# coilcube.net
KiCad netlist of a schematic drawn in EAGLE
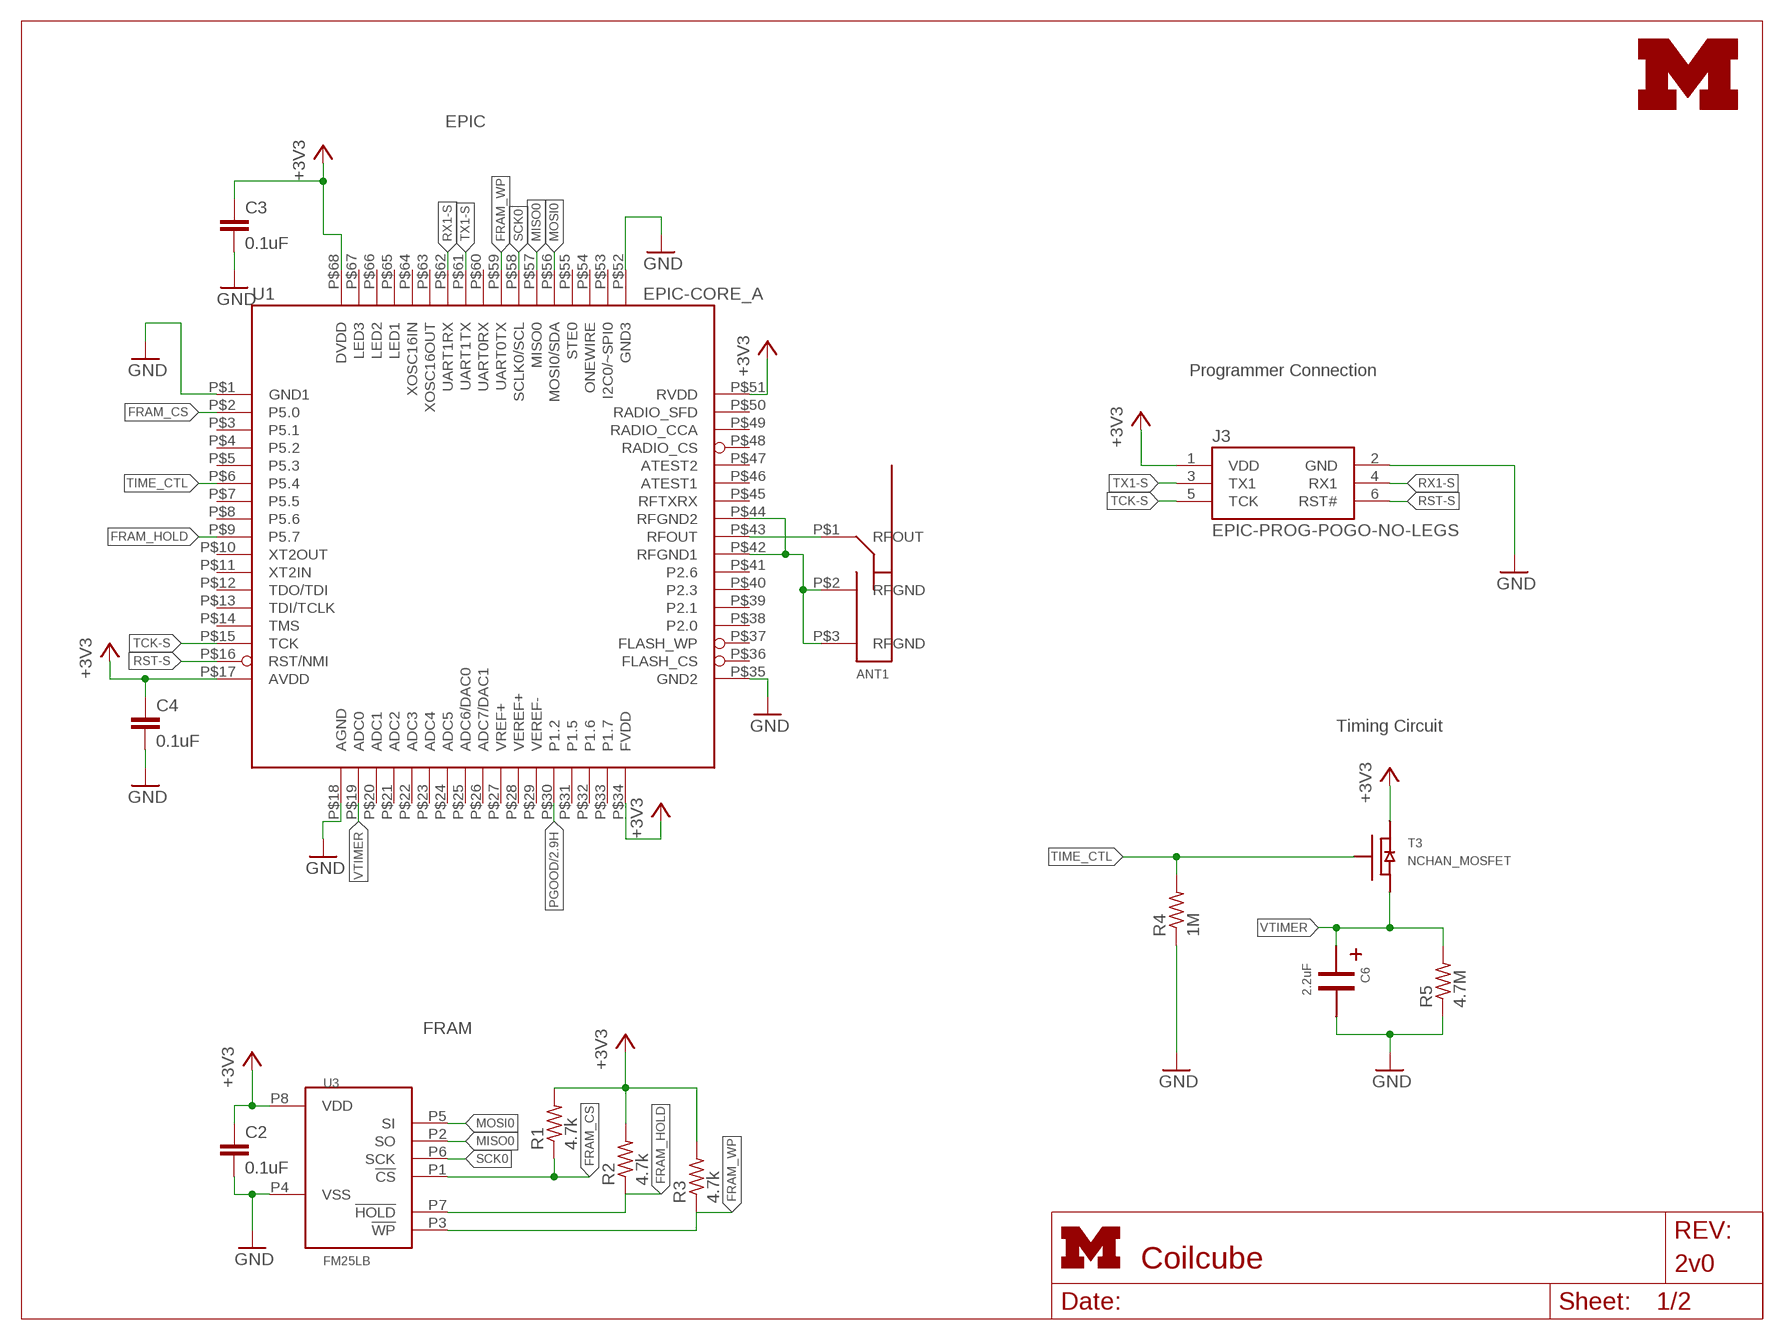
[diagram p0: schematic, sheet 1]
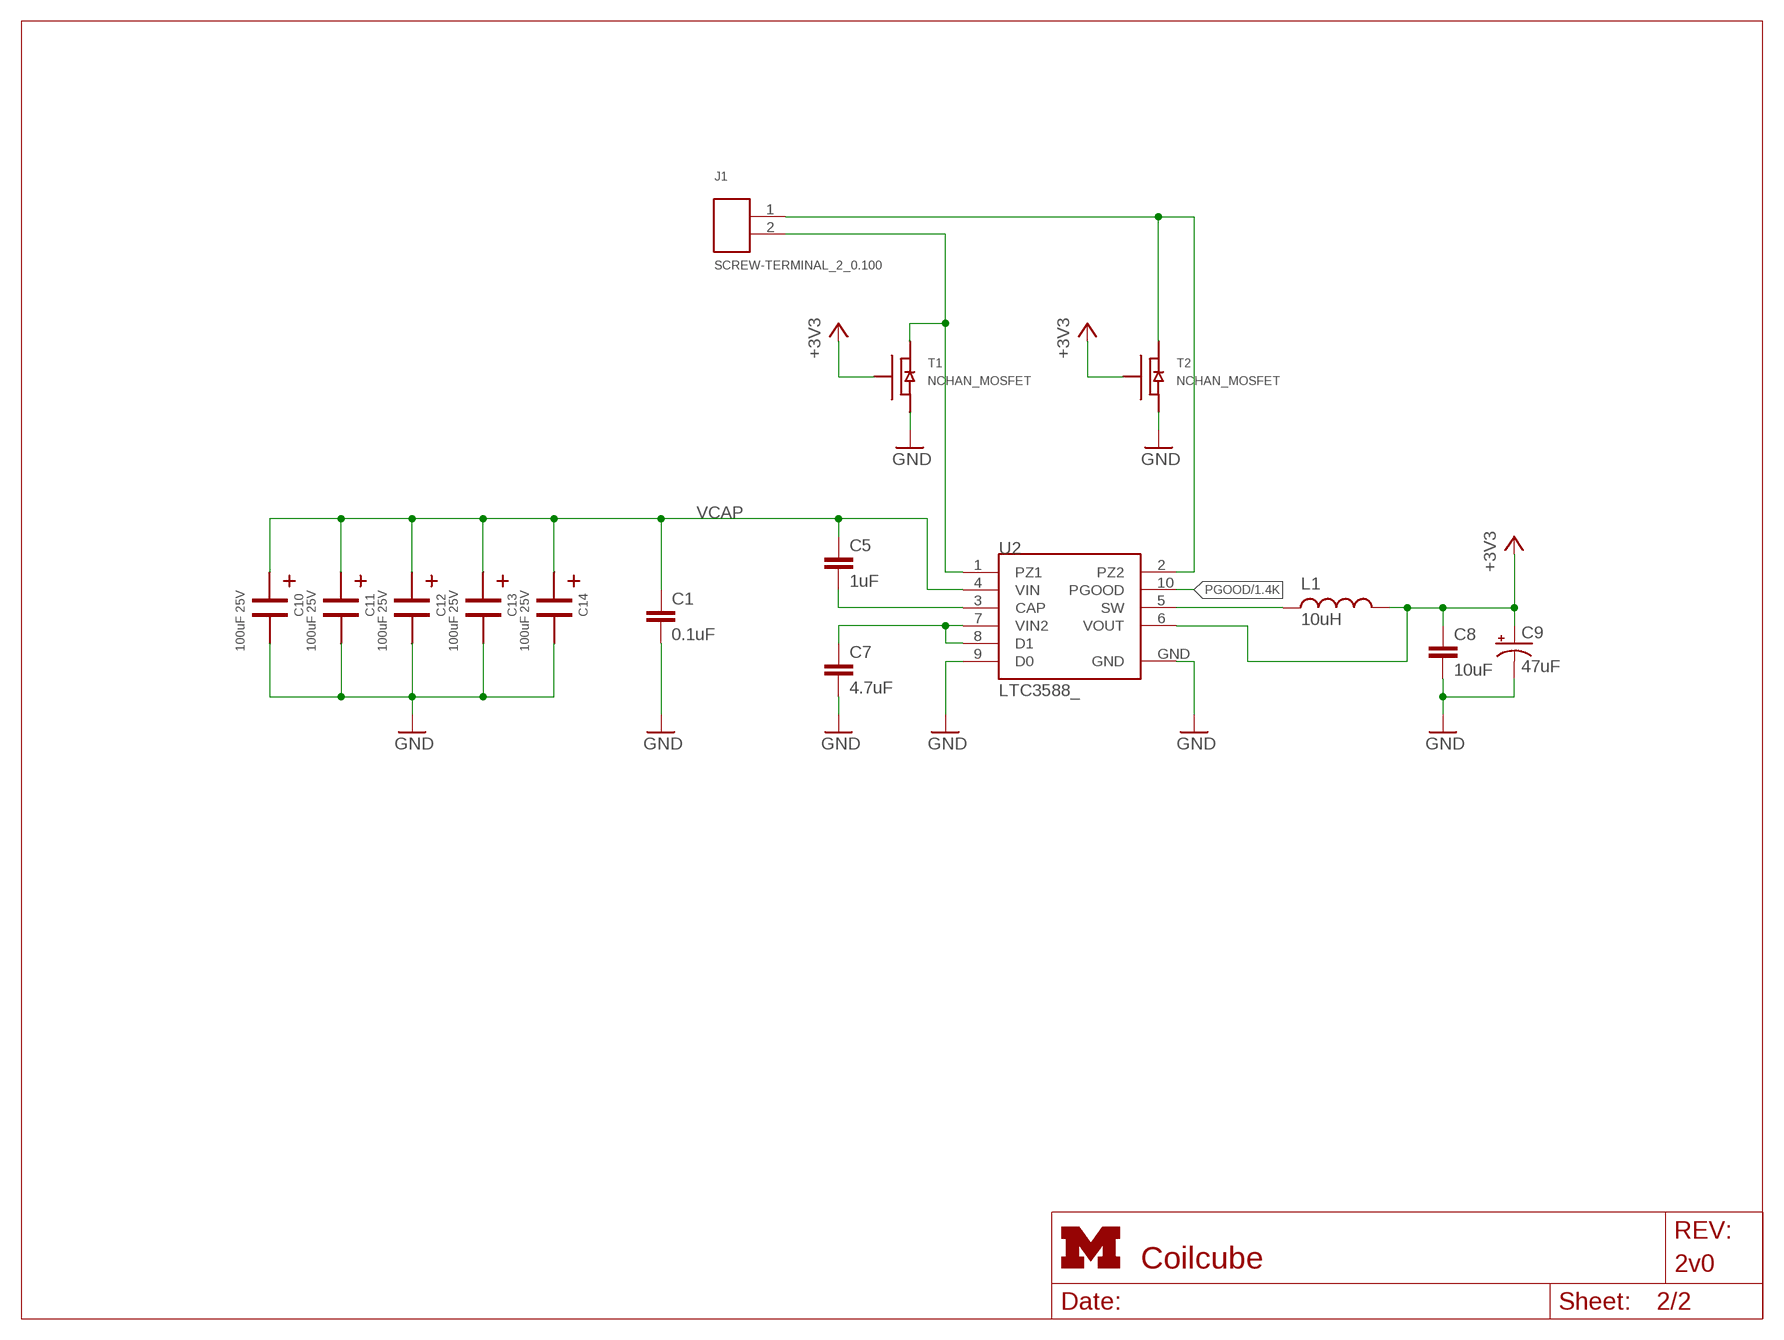
[diagram p1: schematic, sheet 2]

(export (version "E")
  (design (tool "Eeschema 10.0.6"))
  (components
    (comp (ref "ANT1")
      (value "PIFA-2.4GHZ")
      (footprint "eagle-import:PIFA-2.4GHZ")
      (libsource (lib "eagle-import") (part "PIFA-2.4GHZ"))
    )
    (comp (ref "C2")
      (value "0.1uF")
      (footprint "eagle-import:C0603")
      (libsource (lib "eagle-import") (part "C-EUC0603"))
    )
    (comp (ref "C3")
      (value "0.1uF")
      (footprint "eagle-import:C0603")
      (libsource (lib "eagle-import") (part "C-EUC0603"))
    )
    (comp (ref "C4")
      (value "0.1uF")
      (footprint "eagle-import:C0603")
      (libsource (lib "eagle-import") (part "C-EUC0603"))
    )
    (comp (ref "C6")
      (value "2.2uF")
      (footprint "eagle-import:CPOL_EEA_1MM5")
      (libsource (lib "eagle-import") (part "CAP_POLEA1MM5"))
    )
    (comp (ref "J3")
      (value "EPIC-PROG-POGO-NO-LEGS")
      (footprint "eagle-import:TC2030-IDC-NL")
      (libsource (lib "eagle-import") (part "EPIC-PROG-POGO-NO-LEGS"))
    )
    (comp (ref "R1")
      (value "4.7k")
      (footprint "eagle-import:R0603")
      (libsource (lib "eagle-import") (part "R-US_R0603"))
    )
    (comp (ref "R2")
      (value "4.7k")
      (footprint "eagle-import:R0603")
      (libsource (lib "eagle-import") (part "R-US_R0603"))
    )
    (comp (ref "R3")
      (value "4.7k")
      (footprint "eagle-import:R0603")
      (libsource (lib "eagle-import") (part "R-US_R0603"))
    )
    (comp (ref "R4")
      (value "1M")
      (footprint "eagle-import:R0603")
      (libsource (lib "eagle-import") (part "R-US_R0603"))
    )
    (comp (ref "R5")
      (value "4.7M")
      (footprint "eagle-import:R0603")
      (libsource (lib "eagle-import") (part "R-US_R0603"))
    )
    (comp (ref "T3")
      (value "NCHAN_MOSFET")
      (footprint "eagle-import:NCHAN_MOSFET")
      (libsource (lib "eagle-import") (part "NCHAN_MOSFET"))
    )
    (comp (ref "U$1")
      (value "UMICH_SOLID_MEDIUM")
      (footprint "eagle-import:UMICH_SOLID_200MIL")
      (libsource (lib "eagle-import") (part "UMICH_SOLID_MEDIUM"))
    )
    (comp (ref "U1")
      (value "EPIC-CORE_A")
      (footprint "eagle-import:EPIC-LCC68")
      (libsource (lib "eagle-import") (part "EPIC-CORE_A"))
    )
    (comp (ref "U3")
      (value "FM25LB")
      (footprint "eagle-import:SOIC_8")
      (libsource (lib "eagle-import") (part "FM25LB"))
    )
    (comp (ref "C1")
      (value "0.1uF")
      (footprint "eagle-import:C0603")
      (libsource (lib "eagle-import") (part "C-EUC0603"))
    )
    (comp (ref "C5")
      (value "1uF")
      (footprint "eagle-import:C0603")
      (libsource (lib "eagle-import") (part "C-EUC0603"))
    )
    (comp (ref "C7")
      (value "4.7uF")
      (footprint "eagle-import:C0603")
      (libsource (lib "eagle-import") (part "C-EUC0603"))
    )
    (comp (ref "C8")
      (value "10uF")
      (footprint "eagle-import:C1206")
      (libsource (lib "eagle-import") (part "C-EUC1206"))
    )
    (comp (ref "C9")
      (value "47uF")
      (footprint "eagle-import:EIA3216")
      (libsource (lib "eagle-import") (part "CAP_POL1206"))
    )
    (comp (ref "C10")
      (value "100uF 25V")
      (footprint "eagle-import:2917_CAP_POL")
      (libsource (lib "eagle-import") (part "2917_CAP_POL"))
    )
    (comp (ref "C11")
      (value "100uF 25V")
      (footprint "eagle-import:2917_CAP_POL")
      (libsource (lib "eagle-import") (part "2917_CAP_POL"))
    )
    (comp (ref "C12")
      (value "100uF 25V")
      (footprint "eagle-import:2917_CAP_POL")
      (libsource (lib "eagle-import") (part "2917_CAP_POL"))
    )
    (comp (ref "C13")
      (value "100uF 25V")
      (footprint "eagle-import:2917_CAP_POL")
      (libsource (lib "eagle-import") (part "2917_CAP_POL"))
    )
    (comp (ref "C14")
      (value "100uF 25V")
      (footprint "eagle-import:2917_CAP_POL")
      (libsource (lib "eagle-import") (part "2917_CAP_POL"))
    )
    (comp (ref "J1")
      (value "SCREW-TERMINAL_2_0.100")
      (footprint "eagle-import:CONN_BLOCK_2")
      (libsource (lib "eagle-import") (part "SCREW-TERMINAL_2_0.100"))
    )
    (comp (ref "L1")
      (value "10uH")
      (footprint "eagle-import:1210")
      (libsource (lib "eagle-import") (part "INDUCTOR1210"))
    )
    (comp (ref "T1")
      (value "NCHAN_MOSFET")
      (footprint "eagle-import:NCHAN_MOSFET")
      (libsource (lib "eagle-import") (part "NCHAN_MOSFET"))
    )
    (comp (ref "T2")
      (value "NCHAN_MOSFET")
      (footprint "eagle-import:NCHAN_MOSFET")
      (libsource (lib "eagle-import") (part "NCHAN_MOSFET"))
    )
    (comp (ref "U2")
      (value "LTC3588_")
      (footprint "eagle-import:MSOP-10-GNDPAD")
      (libsource (lib "eagle-import") (part "LTC3588_"))
    )
  )
  (nets
    (net (code "1") (name "+3V3") (class "Default")
      (node (ref "C2") (pin "1") (pinfunction "1_1") (pintype "passive"))
      (node (ref "C3") (pin "1") (pinfunction "1_1") (pintype "passive"))
      (node (ref "C4") (pin "1") (pinfunction "1_1") (pintype "passive"))
      (node (ref "C8") (pin "1") (pinfunction "1_1") (pintype "passive"))
      (node (ref "C9") (pin "A") (pinfunction "+_A") (pintype "passive"))
      (node (ref "J3") (pin "1") (pinfunction "VDD_1") (pintype "bidirectional"))
      (node (ref "L1") (pin "2") (pinfunction "2_2") (pintype "passive"))
      (node (ref "R1") (pin "2") (pinfunction "2_2") (pintype "passive"))
      (node (ref "R2") (pin "2") (pinfunction "2_2") (pintype "passive"))
      (node (ref "R3") (pin "2") (pinfunction "2_2") (pintype "passive"))
      (node (ref "T1") (pin "G") (pinfunction "G_G") (pintype "bidirectional"))
      (node (ref "T2") (pin "G") (pinfunction "G_G") (pintype "bidirectional"))
      (node (ref "T3") (pin "D") (pinfunction "D_D") (pintype "bidirectional"))
      (node (ref "U1") (pin "P$17") (pinfunction "AVDD_P$17") (pintype "bidirectional"))
      (node (ref "U1") (pin "P$34") (pinfunction "FVDD_P$34") (pintype "bidirectional"))
      (node (ref "U1") (pin "P$51") (pinfunction "RVDD_P$51") (pintype "bidirectional"))
      (node (ref "U1") (pin "P$68") (pinfunction "DVDD_P$68") (pintype "bidirectional"))
      (node (ref "U2") (pin "6") (pinfunction "VOUT_6") (pintype "bidirectional"))
      (node (ref "U3") (pin "P8") (pinfunction "VDD_P8") (pintype "bidirectional"))
    )
    (net (code "2") (name "FRAM_CS") (class "Default")
      (node (ref "R1") (pin "1") (pinfunction "1_1") (pintype "passive"))
      (node (ref "U1") (pin "P$2") (pinfunction "P5.0_P$2") (pintype "bidirectional"))
      (node (ref "U3") (pin "P1") (pinfunction "~{CS}_P1") (pintype "bidirectional"))
    )
    (net (code "3") (name "FRAM_HOLD") (class "Default")
      (node (ref "R2") (pin "1") (pinfunction "1_1") (pintype "passive"))
      (node (ref "U1") (pin "P$9") (pinfunction "P5.7_P$9") (pintype "bidirectional"))
      (node (ref "U3") (pin "P7") (pinfunction "~{HOLD}_P7") (pintype "bidirectional"))
    )
    (net (code "4") (name "FRAM_WP") (class "Default")
      (node (ref "R3") (pin "1") (pinfunction "1_1") (pintype "passive"))
      (node (ref "U1") (pin "P$59") (pinfunction "UART0TX_P$59") (pintype "bidirectional"))
      (node (ref "U3") (pin "P3") (pinfunction "~{WP}_P3") (pintype "bidirectional"))
    )
    (net (code "5") (name "GND") (class "Default")
      (node (ref "C1") (pin "2") (pinfunction "2_2") (pintype "passive"))
      (node (ref "C10") (pin "-") (pinfunction "-_-") (pintype "bidirectional"))
      (node (ref "C11") (pin "-") (pinfunction "-_-") (pintype "bidirectional"))
      (node (ref "C12") (pin "-") (pinfunction "-_-") (pintype "bidirectional"))
      (node (ref "C13") (pin "-") (pinfunction "-_-") (pintype "bidirectional"))
      (node (ref "C14") (pin "-") (pinfunction "-_-") (pintype "bidirectional"))
      (node (ref "C2") (pin "2") (pinfunction "2_2") (pintype "passive"))
      (node (ref "C3") (pin "2") (pinfunction "2_2") (pintype "passive"))
      (node (ref "C4") (pin "2") (pinfunction "2_2") (pintype "passive"))
      (node (ref "C6") (pin "-") (pinfunction "-_-") (pintype "bidirectional"))
      (node (ref "C7") (pin "2") (pinfunction "2_2") (pintype "passive"))
      (node (ref "C8") (pin "2") (pinfunction "2_2") (pintype "passive"))
      (node (ref "C9") (pin "C") (pinfunction "-_C") (pintype "passive"))
      (node (ref "J3") (pin "2") (pinfunction "GND_2") (pintype "bidirectional"))
      (node (ref "R4") (pin "1") (pinfunction "1_1") (pintype "passive"))
      (node (ref "R5") (pin "1") (pinfunction "1_1") (pintype "passive"))
      (node (ref "T1") (pin "S") (pinfunction "S_S") (pintype "bidirectional"))
      (node (ref "T2") (pin "S") (pinfunction "S_S") (pintype "bidirectional"))
      (node (ref "U1") (pin "P$1") (pinfunction "GND1_P$1") (pintype "bidirectional"))
      (node (ref "U1") (pin "P$18") (pinfunction "AGND_P$18") (pintype "bidirectional"))
      (node (ref "U1") (pin "P$35") (pinfunction "GND2_P$35") (pintype "bidirectional"))
      (node (ref "U1") (pin "P$52") (pinfunction "GND3_P$52") (pintype "bidirectional"))
      (node (ref "U2") (pin "9") (pinfunction "D0_9") (pintype "bidirectional"))
      (node (ref "U2") (pin "GND") (pinfunction "GND_GND") (pintype "bidirectional"))
      (node (ref "U3") (pin "P4") (pinfunction "VSS_P4") (pintype "bidirectional"))
    )
    (net (code "6") (name "MISO0") (class "Default")
      (node (ref "U1") (pin "P$57") (pinfunction "MISO0_P$57") (pintype "bidirectional"))
      (node (ref "U3") (pin "P2") (pinfunction "SO_P2") (pintype "bidirectional"))
    )
    (net (code "7") (name "MOSI0") (class "Default")
      (node (ref "U1") (pin "P$56") (pinfunction "MOSI0/SDA_P$56") (pintype "bidirectional"))
      (node (ref "U3") (pin "P5") (pinfunction "SI_P5") (pintype "bidirectional"))
    )
    (net (code "8") (name "Net-(ANT1-RFOUT)") (class "Default")
      (node (ref "ANT1") (pin "P$1") (pinfunction "RFOUT_P$1") (pintype "bidirectional"))
      (node (ref "U1") (pin "P$43") (pinfunction "RFOUT_P$43") (pintype "bidirectional"))
    )
    (net (code "9") (name "Net-(U1-RFGND1)") (class "Default")
      (node (ref "ANT1") (pin "P$2") (pinfunction "RFGND_P$2") (pintype "bidirectional"))
      (node (ref "ANT1") (pin "P$3") (pinfunction "RFGND_P$3") (pintype "bidirectional"))
      (node (ref "U1") (pin "P$42") (pinfunction "RFGND1_P$42") (pintype "bidirectional"))
      (node (ref "U1") (pin "P$44") (pinfunction "RFGND2_P$44") (pintype "bidirectional"))
    )
    (net (code "10") (name "Net-(U2-CAP)") (class "Default")
      (node (ref "C5") (pin "2") (pinfunction "2_2") (pintype "passive"))
      (node (ref "U2") (pin "3") (pinfunction "CAP_3") (pintype "bidirectional"))
    )
    (net (code "11") (name "Net-(U2-D1)") (class "Default")
      (node (ref "C7") (pin "1") (pinfunction "1_1") (pintype "passive"))
      (node (ref "U2") (pin "7") (pinfunction "VIN2_7") (pintype "bidirectional"))
      (node (ref "U2") (pin "8") (pinfunction "D1_8") (pintype "bidirectional"))
    )
    (net (code "12") (name "Net-(U2-PZ1)") (class "Default")
      (node (ref "J1") (pin "2") (pinfunction "2_2") (pintype "bidirectional"))
      (node (ref "T1") (pin "D") (pinfunction "D_D") (pintype "bidirectional"))
      (node (ref "U2") (pin "1") (pinfunction "PZ1_1") (pintype "bidirectional"))
    )
    (net (code "13") (name "Net-(U2-PZ2)") (class "Default")
      (node (ref "J1") (pin "1") (pinfunction "1_1") (pintype "bidirectional"))
      (node (ref "T2") (pin "D") (pinfunction "D_D") (pintype "bidirectional"))
      (node (ref "U2") (pin "2") (pinfunction "PZ2_2") (pintype "bidirectional"))
    )
    (net (code "14") (name "Net-(U2-SW)") (class "Default")
      (node (ref "L1") (pin "1") (pinfunction "1_1") (pintype "passive"))
      (node (ref "U2") (pin "5") (pinfunction "SW_5") (pintype "bidirectional"))
    )
    (net (code "15") (name "PGOOD") (class "Default")
      (node (ref "U1") (pin "P$30") (pinfunction "P1.2_P$30") (pintype "bidirectional"))
      (node (ref "U2") (pin "10") (pinfunction "PGOOD_10") (pintype "bidirectional"))
    )
    (net (code "16") (name "RST-S") (class "Default")
      (node (ref "J3") (pin "6") (pinfunction "RST#_6") (pintype "bidirectional"))
      (node (ref "U1") (pin "P$16") (pinfunction "RST/NMI_P$16") (pintype "bidirectional"))
    )
    (net (code "17") (name "RX1-S") (class "Default")
      (node (ref "J3") (pin "4") (pinfunction "RX1_4") (pintype "bidirectional"))
      (node (ref "U1") (pin "P$62") (pinfunction "UART1RX_P$62") (pintype "bidirectional"))
    )
    (net (code "18") (name "SCK0") (class "Default")
      (node (ref "U1") (pin "P$58") (pinfunction "SCLK0/SCL_P$58") (pintype "bidirectional"))
      (node (ref "U3") (pin "P6") (pinfunction "SCK_P6") (pintype "bidirectional"))
    )
    (net (code "19") (name "TCK-S") (class "Default")
      (node (ref "J3") (pin "5") (pinfunction "TCK_5") (pintype "bidirectional"))
      (node (ref "U1") (pin "P$15") (pinfunction "TCK_P$15") (pintype "bidirectional"))
    )
    (net (code "20") (name "TIME_CTL") (class "Default")
      (node (ref "R4") (pin "2") (pinfunction "2_2") (pintype "passive"))
      (node (ref "T3") (pin "G") (pinfunction "G_G") (pintype "bidirectional"))
      (node (ref "U1") (pin "P$6") (pinfunction "P5.4_P$6") (pintype "bidirectional"))
    )
    (net (code "21") (name "TX1-S") (class "Default")
      (node (ref "J3") (pin "3") (pinfunction "TX1_3") (pintype "bidirectional"))
      (node (ref "U1") (pin "P$61") (pinfunction "UART1TX_P$61") (pintype "bidirectional"))
    )
    (net (code "22") (name "VCAP") (class "Default")
      (node (ref "C1") (pin "1") (pinfunction "1_1") (pintype "passive"))
      (node (ref "C10") (pin "+") (pinfunction "+_+") (pintype "bidirectional"))
      (node (ref "C11") (pin "+") (pinfunction "+_+") (pintype "bidirectional"))
      (node (ref "C12") (pin "+") (pinfunction "+_+") (pintype "bidirectional"))
      (node (ref "C13") (pin "+") (pinfunction "+_+") (pintype "bidirectional"))
      (node (ref "C14") (pin "+") (pinfunction "+_+") (pintype "bidirectional"))
      (node (ref "C5") (pin "1") (pinfunction "1_1") (pintype "passive"))
      (node (ref "U2") (pin "4") (pinfunction "VIN_4") (pintype "bidirectional"))
    )
    (net (code "23") (name "VTIMER") (class "Default")
      (node (ref "C6") (pin "+") (pinfunction "+_+") (pintype "bidirectional"))
      (node (ref "R5") (pin "2") (pinfunction "2_2") (pintype "passive"))
      (node (ref "T3") (pin "S") (pinfunction "S_S") (pintype "bidirectional"))
      (node (ref "U1") (pin "P$19") (pinfunction "ADC0_P$19") (pintype "bidirectional"))
    )
    (net (code "24") (name "unconnected-(U1-ADC1-PadP$20)") (class "Default")
      (node (ref "U1") (pin "P$20") (pinfunction "ADC1_P$20") (pintype "bidirectional"))
    )
    (net (code "25") (name "unconnected-(U1-ADC2-PadP$21)") (class "Default")
      (node (ref "U1") (pin "P$21") (pinfunction "ADC2_P$21") (pintype "bidirectional"))
    )
    (net (code "26") (name "unconnected-(U1-ADC3-PadP$22)") (class "Default")
      (node (ref "U1") (pin "P$22") (pinfunction "ADC3_P$22") (pintype "bidirectional"))
    )
    (net (code "27") (name "unconnected-(U1-ADC4-PadP$23)") (class "Default")
      (node (ref "U1") (pin "P$23") (pinfunction "ADC4_P$23") (pintype "bidirectional"))
    )
    (net (code "28") (name "unconnected-(U1-ADC5-PadP$24)") (class "Default")
      (node (ref "U1") (pin "P$24") (pinfunction "ADC5_P$24") (pintype "bidirectional"))
    )
    (net (code "29") (name "unconnected-(U1-ADC6{slash}DAC0-PadP$25)") (class "Default")
      (node (ref "U1") (pin "P$25") (pinfunction "ADC6/DAC0_P$25") (pintype "bidirectional"))
    )
    (net (code "30") (name "unconnected-(U1-ADC7{slash}DAC1-PadP$26)") (class "Default")
      (node (ref "U1") (pin "P$26") (pinfunction "ADC7/DAC1_P$26") (pintype "bidirectional"))
    )
    (net (code "31") (name "unconnected-(U1-ATEST1-PadP$46)") (class "Default")
      (node (ref "U1") (pin "P$46") (pinfunction "ATEST1_P$46") (pintype "bidirectional"))
    )
    (net (code "32") (name "unconnected-(U1-ATEST2-PadP$47)") (class "Default")
      (node (ref "U1") (pin "P$47") (pinfunction "ATEST2_P$47") (pintype "bidirectional"))
    )
    (net (code "33") (name "unconnected-(U1-FLASH_CS-PadP$36)") (class "Default")
      (node (ref "U1") (pin "P$36") (pinfunction "FLASH_CS_P$36") (pintype "bidirectional"))
    )
    (net (code "34") (name "unconnected-(U1-FLASH_WP-PadP$37)") (class "Default")
      (node (ref "U1") (pin "P$37") (pinfunction "FLASH_WP_P$37") (pintype "bidirectional"))
    )
    (net (code "35") (name "unconnected-(U1-I2C0{slash}~{SPI0}-PadP$53)") (class "Default")
      (node (ref "U1") (pin "P$53") (pinfunction "I2C0/~{SPI0}_P$53") (pintype "bidirectional"))
    )
    (net (code "36") (name "unconnected-(U1-LED1-PadP$65)") (class "Default")
      (node (ref "U1") (pin "P$65") (pinfunction "LED1_P$65") (pintype "bidirectional"))
    )
    (net (code "37") (name "unconnected-(U1-LED2-PadP$66)") (class "Default")
      (node (ref "U1") (pin "P$66") (pinfunction "LED2_P$66") (pintype "bidirectional"))
    )
    (net (code "38") (name "unconnected-(U1-LED3-PadP$67)") (class "Default")
      (node (ref "U1") (pin "P$67") (pinfunction "LED3_P$67") (pintype "bidirectional"))
    )
    (net (code "39") (name "unconnected-(U1-ONEWIRE-PadP$54)") (class "Default")
      (node (ref "U1") (pin "P$54") (pinfunction "ONEWIRE_P$54") (pintype "bidirectional"))
    )
    (net (code "40") (name "unconnected-(U1-P1.5-PadP$31)") (class "Default")
      (node (ref "U1") (pin "P$31") (pinfunction "P1.5_P$31") (pintype "bidirectional"))
    )
    (net (code "41") (name "unconnected-(U1-P1.6-PadP$32)") (class "Default")
      (node (ref "U1") (pin "P$32") (pinfunction "P1.6_P$32") (pintype "bidirectional"))
    )
    (net (code "42") (name "unconnected-(U1-P1.7-PadP$33)") (class "Default")
      (node (ref "U1") (pin "P$33") (pinfunction "P1.7_P$33") (pintype "bidirectional"))
    )
    (net (code "43") (name "unconnected-(U1-P2.0-PadP$38)") (class "Default")
      (node (ref "U1") (pin "P$38") (pinfunction "P2.0_P$38") (pintype "bidirectional"))
    )
    (net (code "44") (name "unconnected-(U1-P2.1-PadP$39)") (class "Default")
      (node (ref "U1") (pin "P$39") (pinfunction "P2.1_P$39") (pintype "bidirectional"))
    )
    (net (code "45") (name "unconnected-(U1-P2.3-PadP$40)") (class "Default")
      (node (ref "U1") (pin "P$40") (pinfunction "P2.3_P$40") (pintype "bidirectional"))
    )
    (net (code "46") (name "unconnected-(U1-P2.6-PadP$41)") (class "Default")
      (node (ref "U1") (pin "P$41") (pinfunction "P2.6_P$41") (pintype "bidirectional"))
    )
    (net (code "47") (name "unconnected-(U1-P5.1-PadP$3)") (class "Default")
      (node (ref "U1") (pin "P$3") (pinfunction "P5.1_P$3") (pintype "bidirectional"))
    )
    (net (code "48") (name "unconnected-(U1-P5.2-PadP$4)") (class "Default")
      (node (ref "U1") (pin "P$4") (pinfunction "P5.2_P$4") (pintype "bidirectional"))
    )
    (net (code "49") (name "unconnected-(U1-P5.3-PadP$5)") (class "Default")
      (node (ref "U1") (pin "P$5") (pinfunction "P5.3_P$5") (pintype "bidirectional"))
    )
    (net (code "50") (name "unconnected-(U1-P5.5-PadP$7)") (class "Default")
      (node (ref "U1") (pin "P$7") (pinfunction "P5.5_P$7") (pintype "bidirectional"))
    )
    (net (code "51") (name "unconnected-(U1-P5.6-PadP$8)") (class "Default")
      (node (ref "U1") (pin "P$8") (pinfunction "P5.6_P$8") (pintype "bidirectional"))
    )
    (net (code "52") (name "unconnected-(U1-RADIO_CCA-PadP$49)") (class "Default")
      (node (ref "U1") (pin "P$49") (pinfunction "RADIO_CCA_P$49") (pintype "bidirectional"))
    )
    (net (code "53") (name "unconnected-(U1-RADIO_CS-PadP$48)") (class "Default")
      (node (ref "U1") (pin "P$48") (pinfunction "RADIO_CS_P$48") (pintype "bidirectional"))
    )
    (net (code "54") (name "unconnected-(U1-RADIO_SFD-PadP$50)") (class "Default")
      (node (ref "U1") (pin "P$50") (pinfunction "RADIO_SFD_P$50") (pintype "bidirectional"))
    )
    (net (code "55") (name "unconnected-(U1-RFTXRX-PadP$45)") (class "Default")
      (node (ref "U1") (pin "P$45") (pinfunction "RFTXRX_P$45") (pintype "bidirectional"))
    )
    (net (code "56") (name "unconnected-(U1-STE0-PadP$55)") (class "Default")
      (node (ref "U1") (pin "P$55") (pinfunction "STE0_P$55") (pintype "bidirectional"))
    )
    (net (code "57") (name "unconnected-(U1-TDI{slash}TCLK-PadP$13)") (class "Default")
      (node (ref "U1") (pin "P$13") (pinfunction "TDI/TCLK_P$13") (pintype "bidirectional"))
    )
    (net (code "58") (name "unconnected-(U1-TDO{slash}TDI-PadP$12)") (class "Default")
      (node (ref "U1") (pin "P$12") (pinfunction "TDO/TDI_P$12") (pintype "bidirectional"))
    )
    (net (code "59") (name "unconnected-(U1-TMS-PadP$14)") (class "Default")
      (node (ref "U1") (pin "P$14") (pinfunction "TMS_P$14") (pintype "bidirectional"))
    )
    (net (code "60") (name "unconnected-(U1-UART0RX-PadP$60)") (class "Default")
      (node (ref "U1") (pin "P$60") (pinfunction "UART0RX_P$60") (pintype "bidirectional"))
    )
    (net (code "61") (name "unconnected-(U1-VEREF+-PadP$28)") (class "Default")
      (node (ref "U1") (pin "P$28") (pinfunction "VEREF+_P$28") (pintype "bidirectional"))
    )
    (net (code "62") (name "unconnected-(U1-VEREF--PadP$29)") (class "Default")
      (node (ref "U1") (pin "P$29") (pinfunction "VEREF-_P$29") (pintype "bidirectional"))
    )
    (net (code "63") (name "unconnected-(U1-VREF+-PadP$27)") (class "Default")
      (node (ref "U1") (pin "P$27") (pinfunction "VREF+_P$27") (pintype "bidirectional"))
    )
    (net (code "64") (name "unconnected-(U1-XOSC16IN-PadP$64)") (class "Default")
      (node (ref "U1") (pin "P$64") (pinfunction "XOSC16IN_P$64") (pintype "bidirectional"))
    )
    (net (code "65") (name "unconnected-(U1-XOSC16OUT-PadP$63)") (class "Default")
      (node (ref "U1") (pin "P$63") (pinfunction "XOSC16OUT_P$63") (pintype "bidirectional"))
    )
    (net (code "66") (name "unconnected-(U1-XT2IN-PadP$11)") (class "Default")
      (node (ref "U1") (pin "P$11") (pinfunction "XT2IN_P$11") (pintype "bidirectional"))
    )
    (net (code "67") (name "unconnected-(U1-XT2OUT-PadP$10)") (class "Default")
      (node (ref "U1") (pin "P$10") (pinfunction "XT2OUT_P$10") (pintype "bidirectional"))
    )
  )
)
